# board.net
KiCad netlist of a schematic drawn in EAGLE
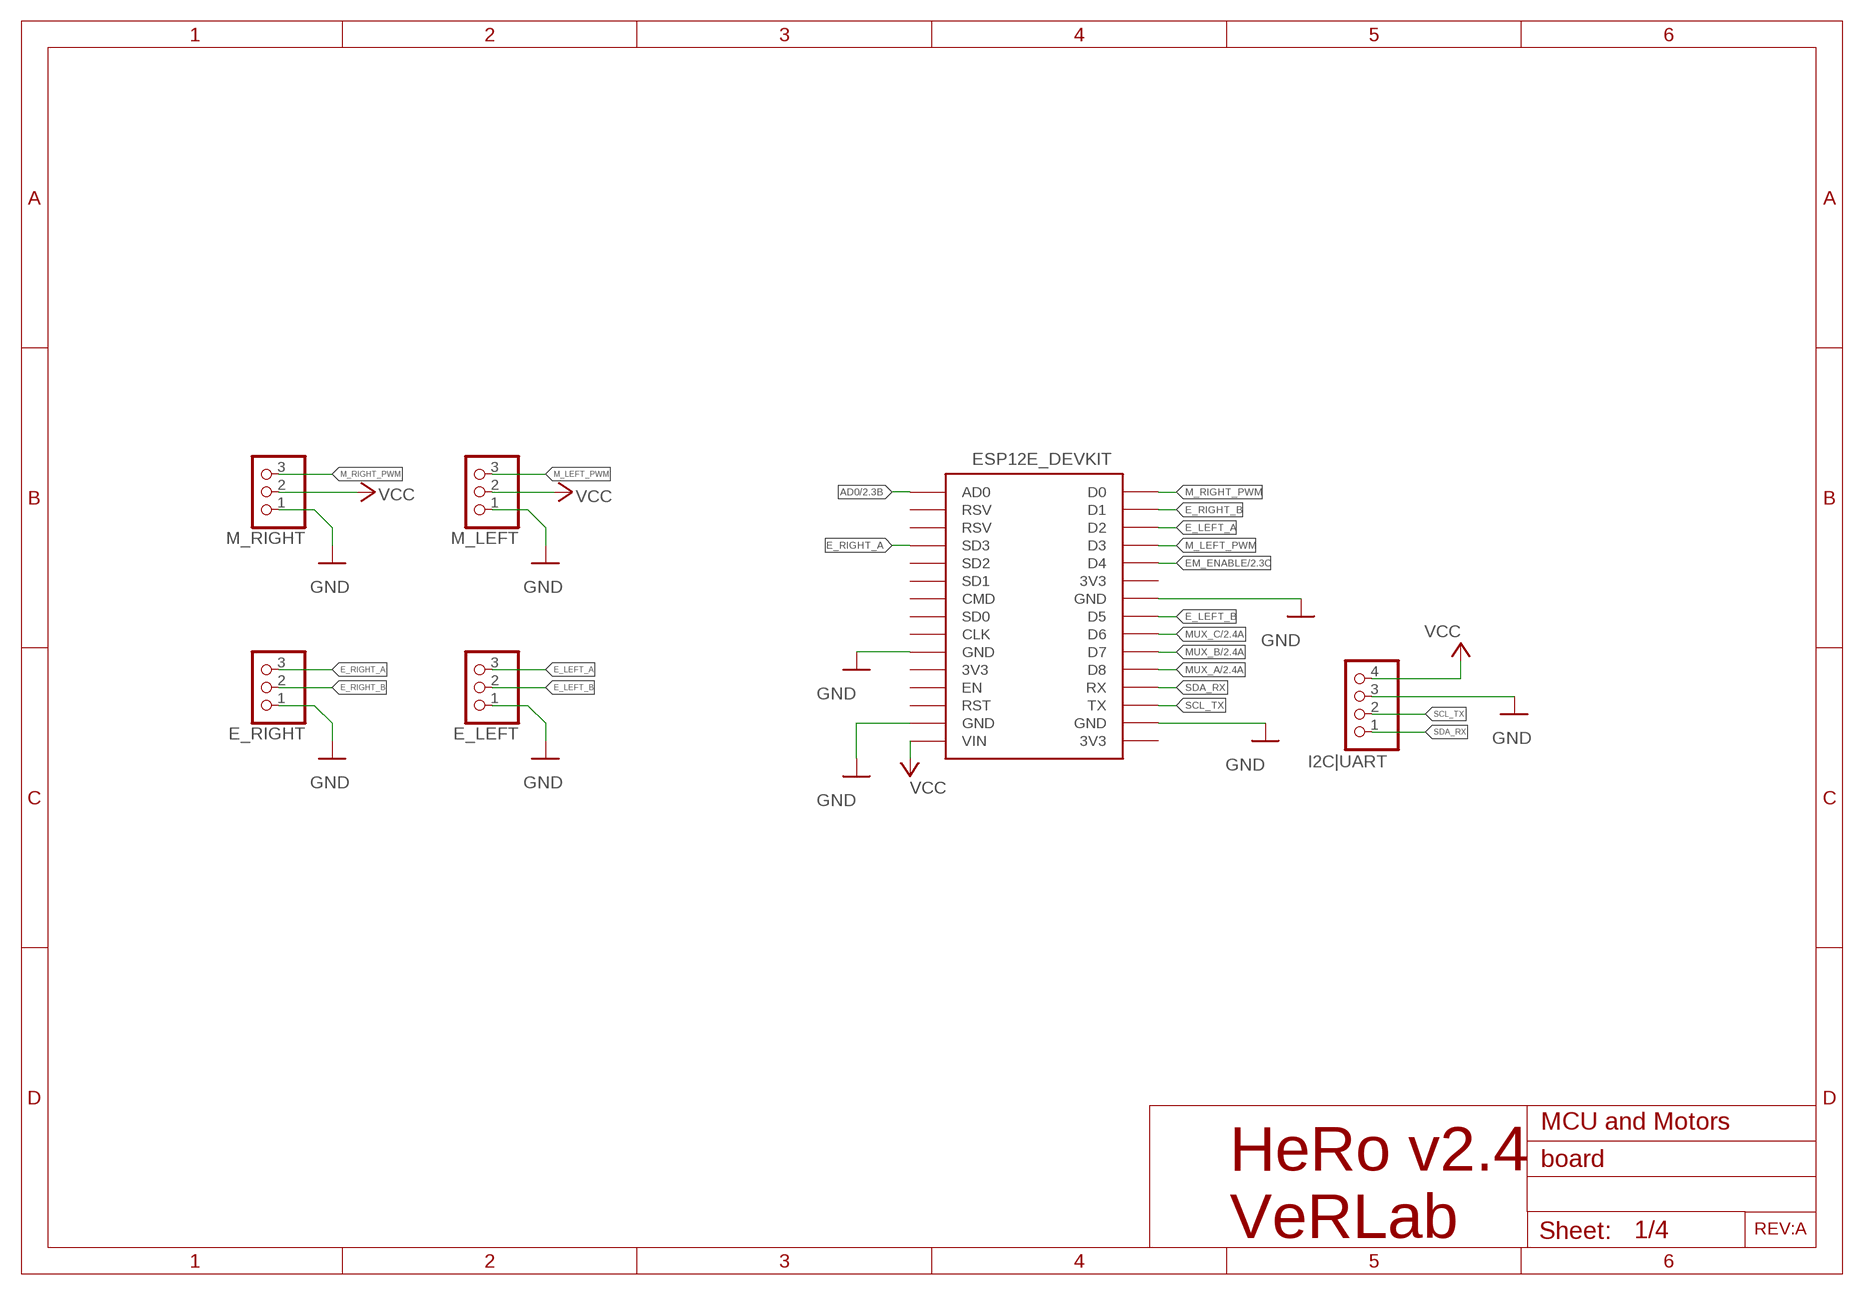
[diagram p0: schematic, sheet 1]
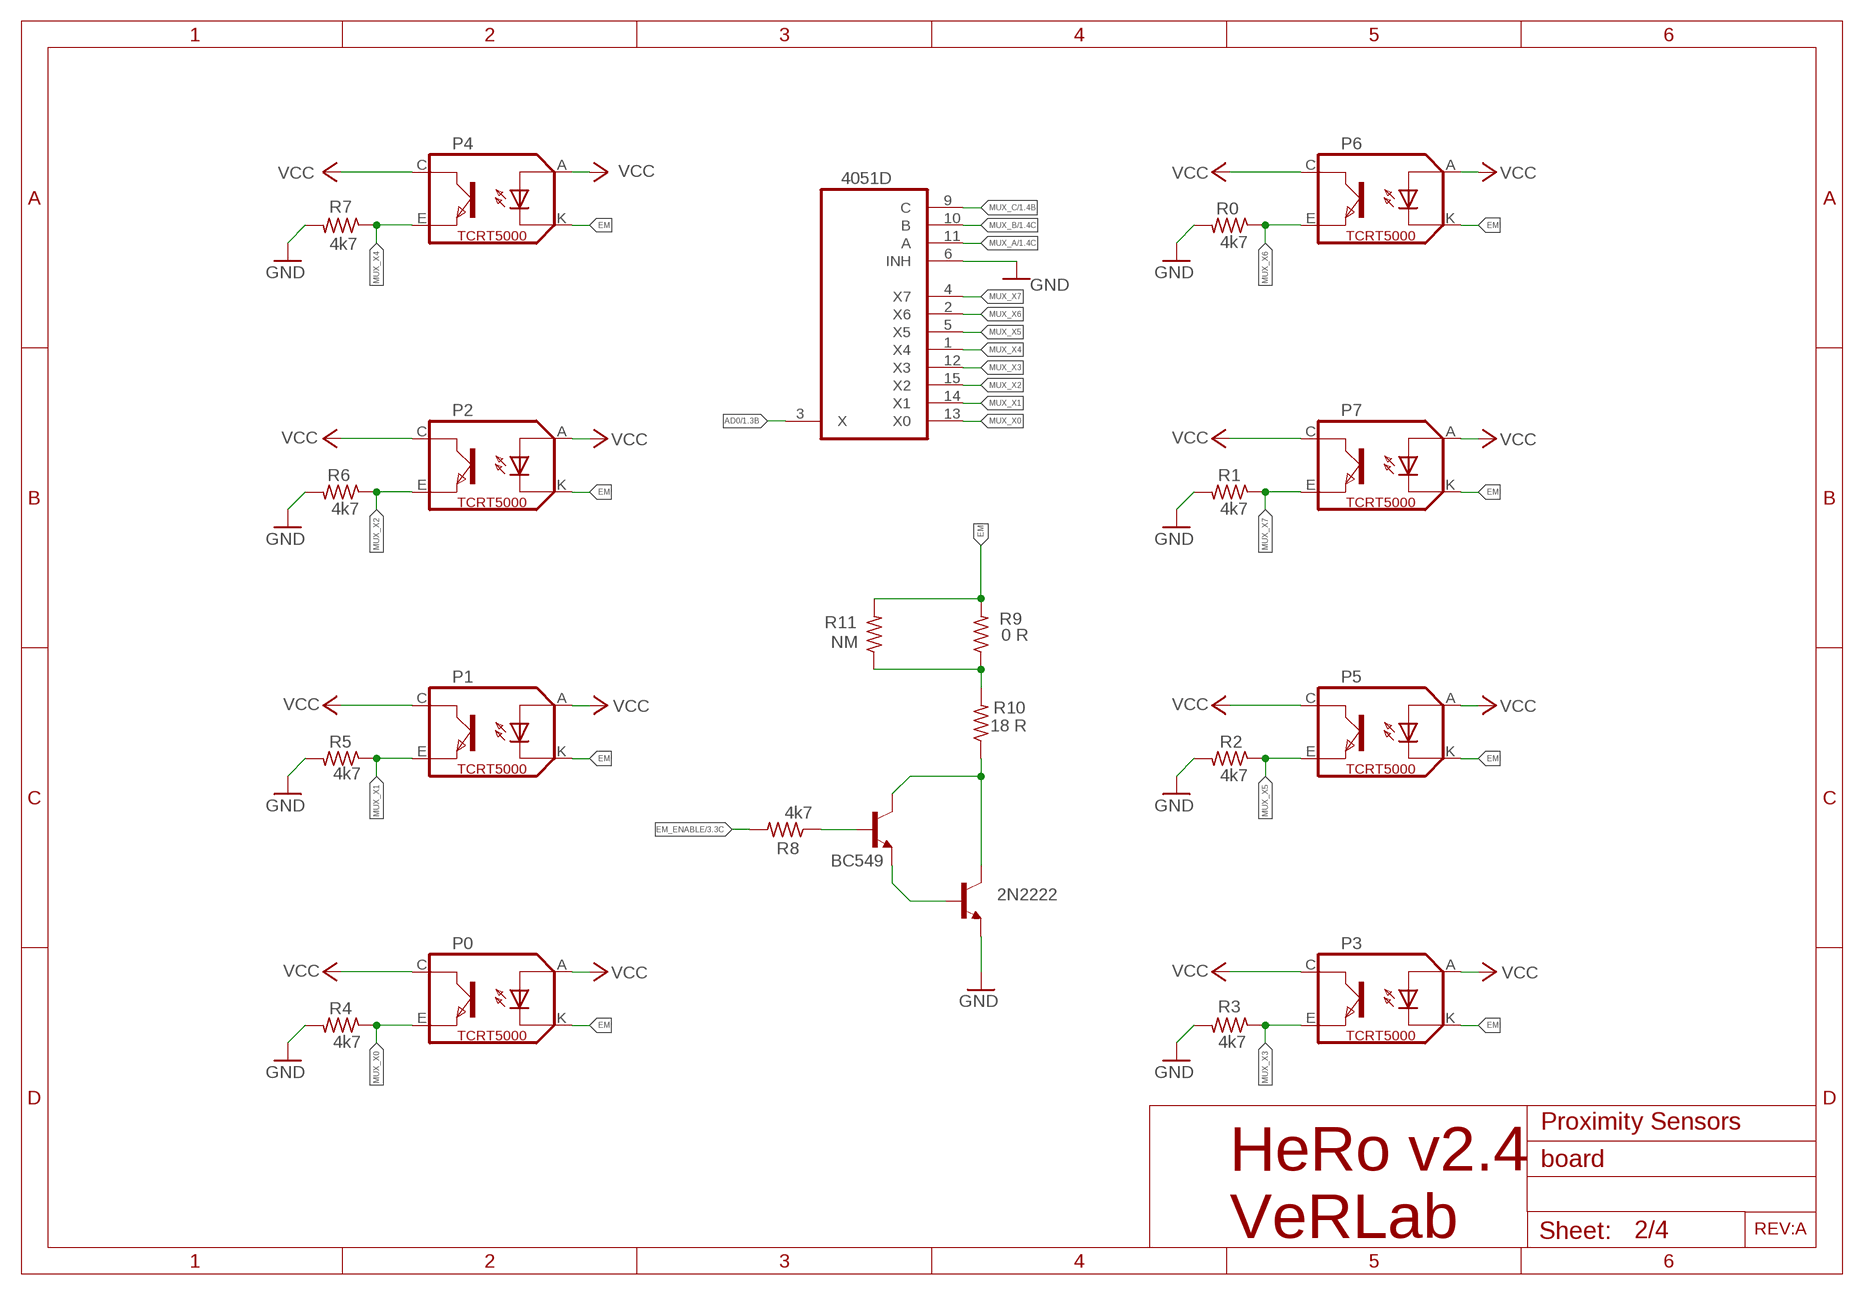
[diagram p1: schematic, sheet 2]
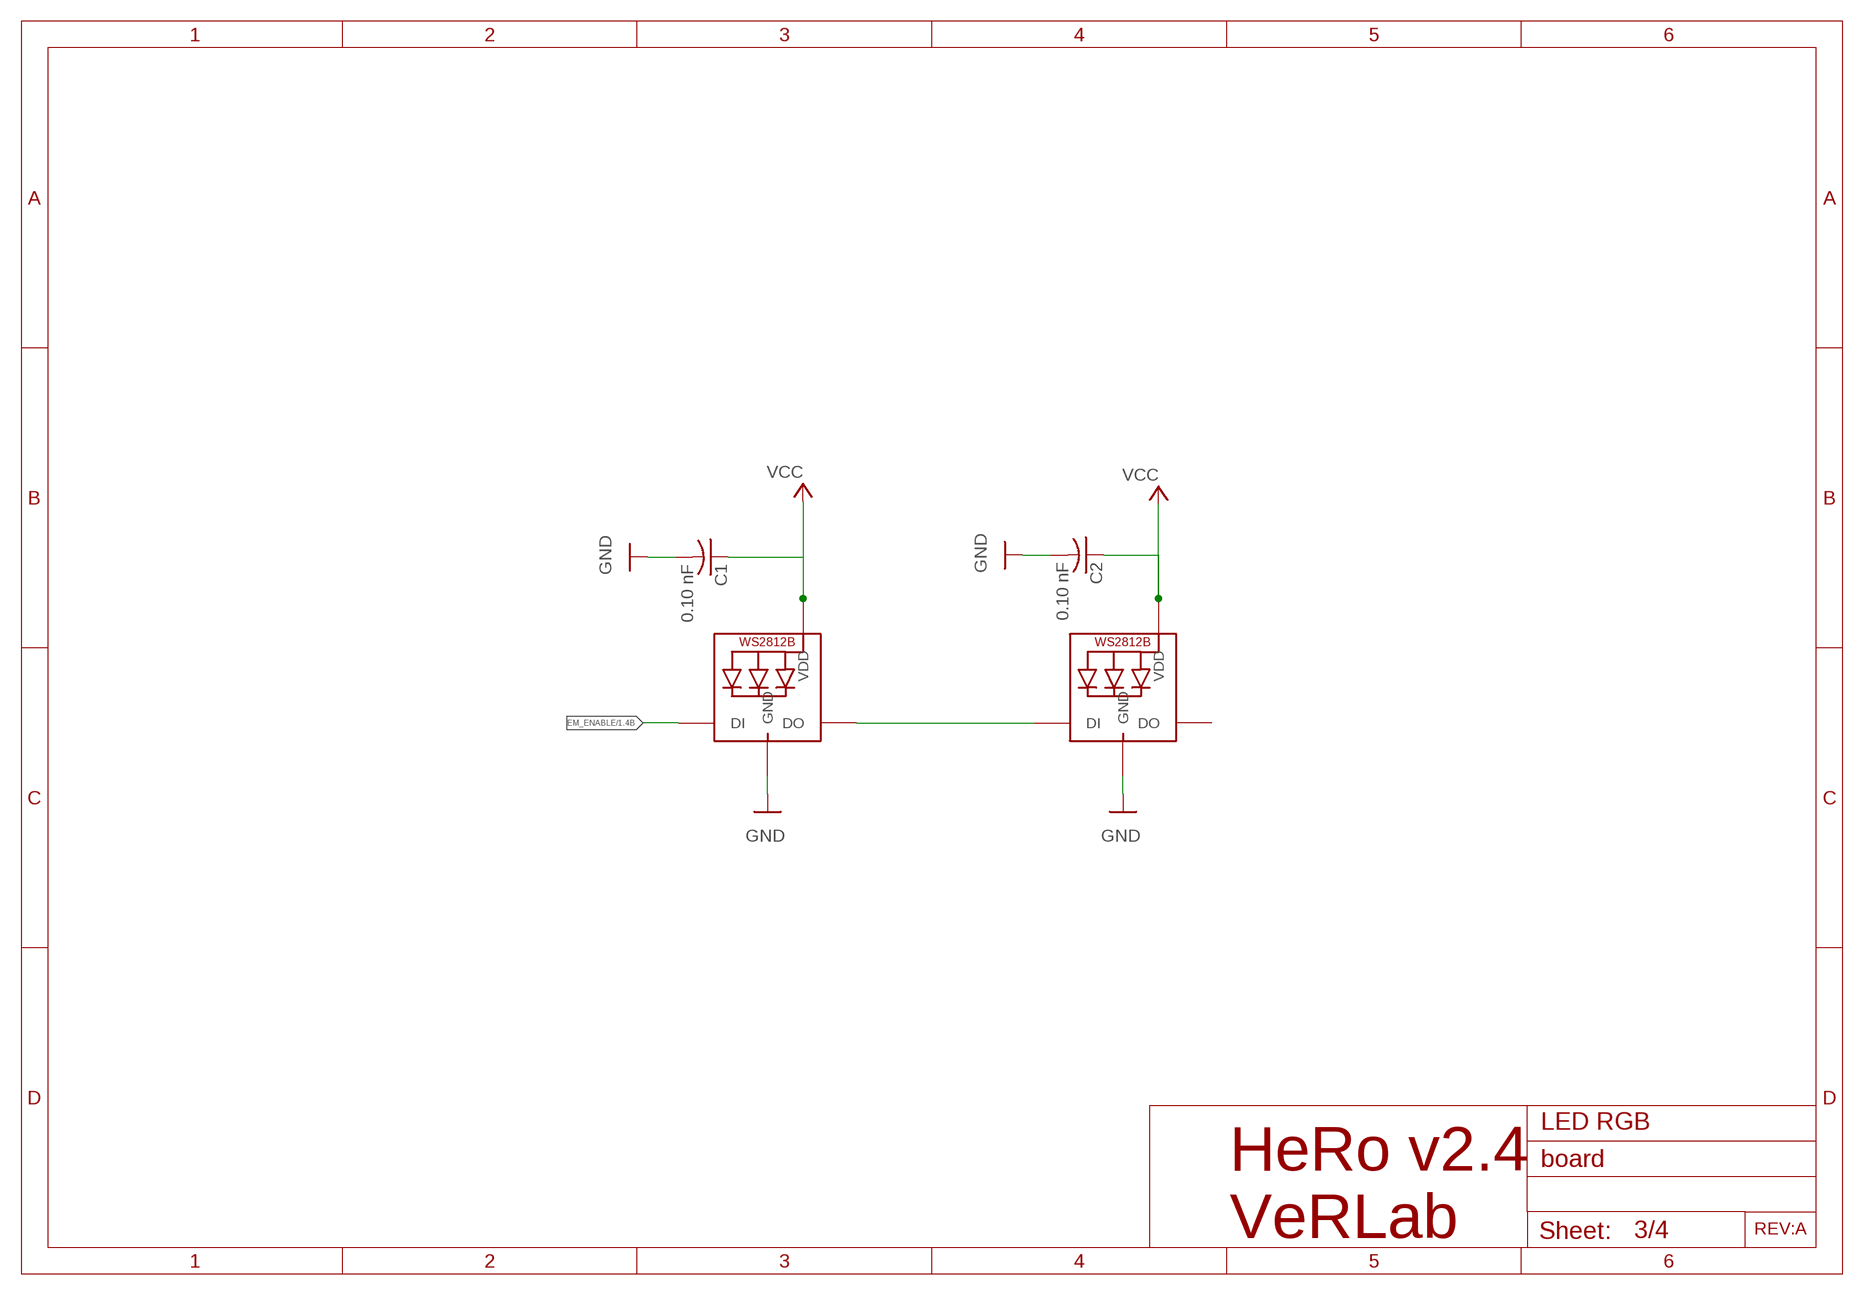
[diagram p2: schematic, sheet 3]
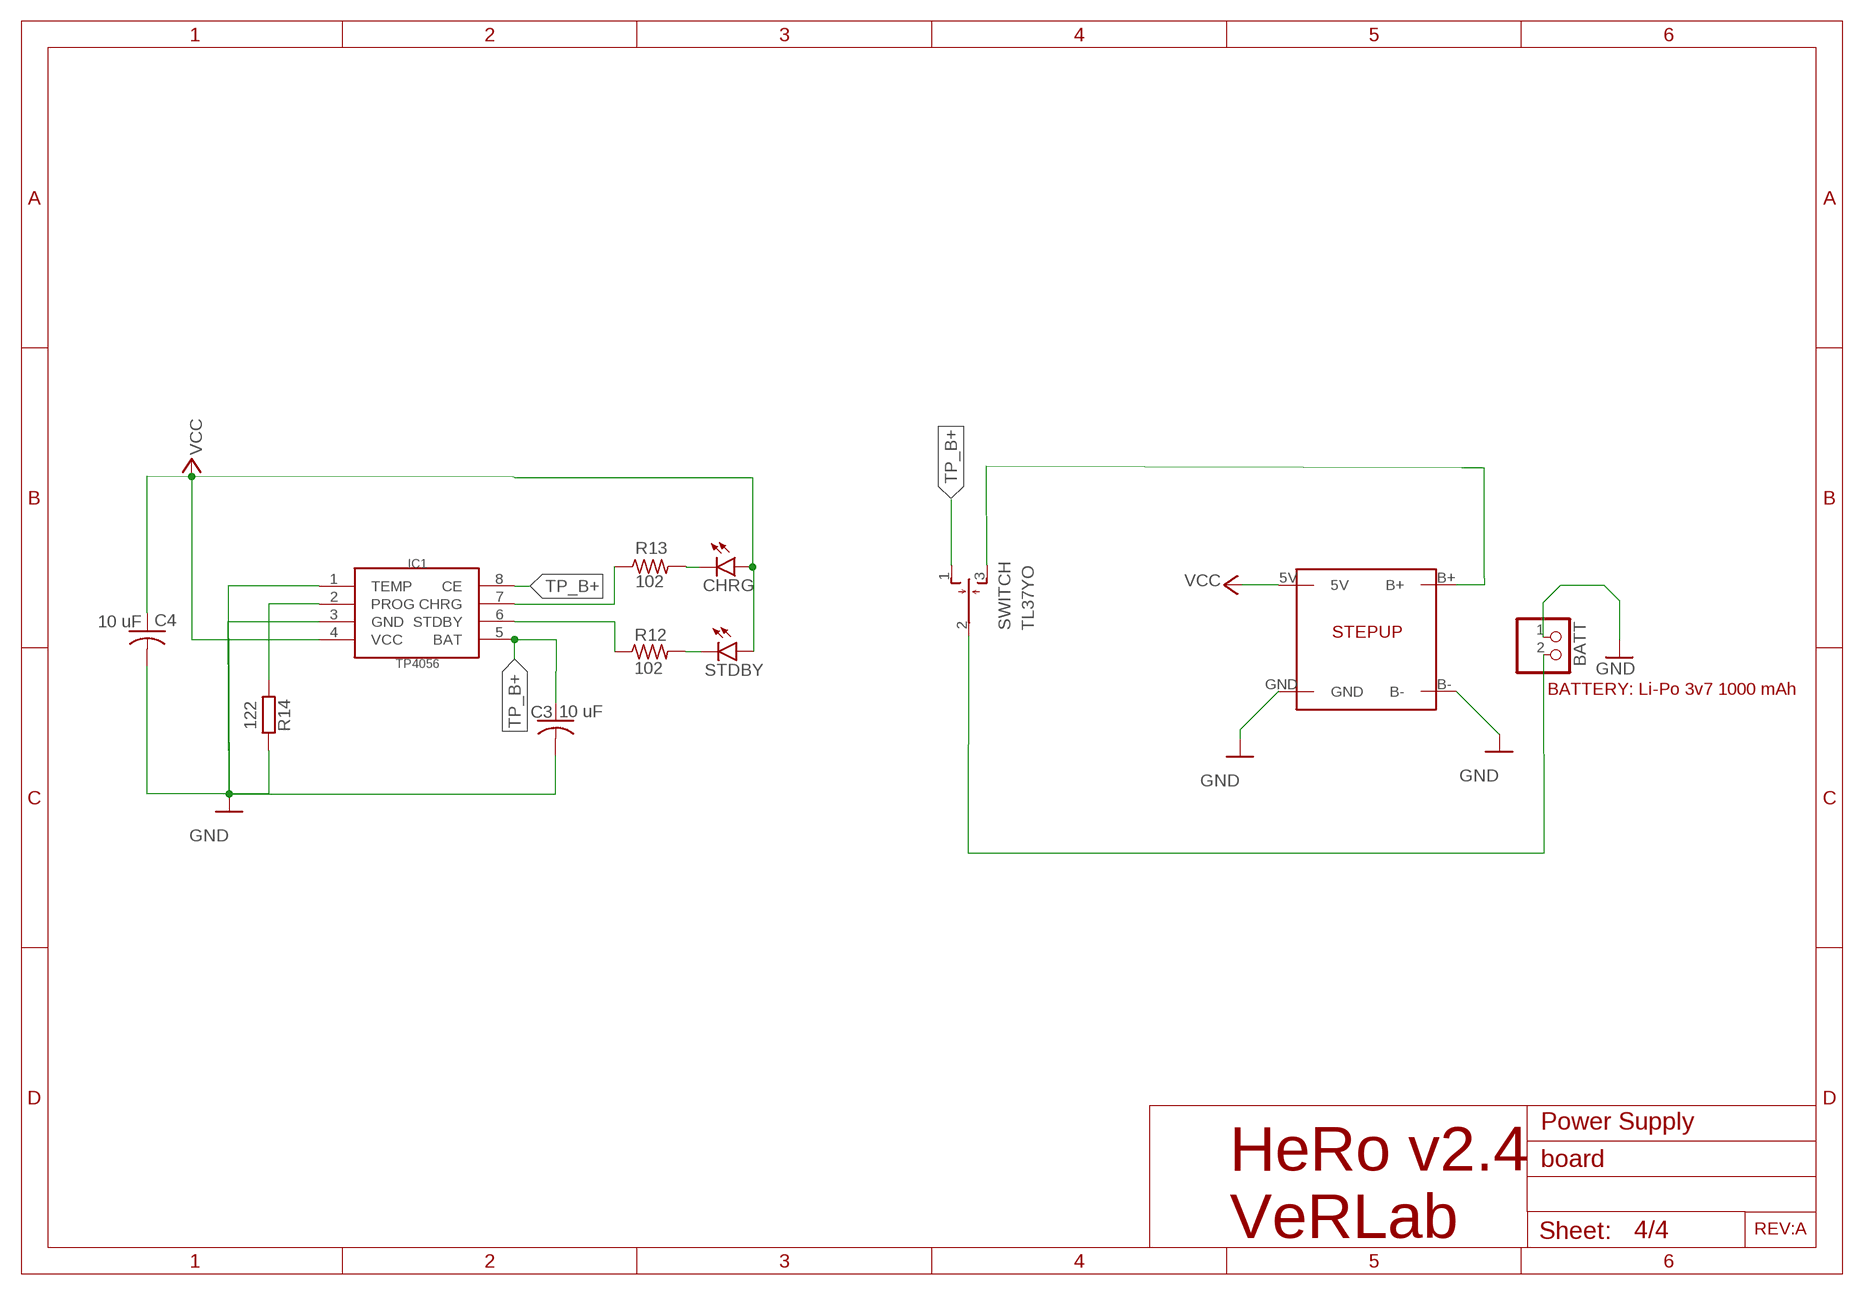
[diagram p3: schematic, sheet 4]

(export (version "E")
  (design (tool "Eeschema 10.0.6"))
  (components
    (comp (ref "C1")
      (value "0.10 nF")
      (footprint "eagle-import:C0603")
      (libsource (lib "eagle-import") (part "C-USC0603"))
    )
    (comp (ref "C2")
      (value "0.10 nF")
      (footprint "eagle-import:C0603")
      (libsource (lib "eagle-import") (part "C-USC0603"))
    )
    (comp (ref "LED0")
      (value "WS2812B5050")
      (footprint "eagle-import:WS2812B")
      (libsource (lib "eagle-import") (part "WS2812B5050"))
    )
    (comp (ref "LED1")
      (value "WS2812B5050")
      (footprint "eagle-import:WS2812B")
      (libsource (lib "eagle-import") (part "WS2812B5050"))
    )
    (comp (ref "BATT")
      (value "PINHD-1X2")
      (footprint "eagle-import:1X02")
      (libsource (lib "eagle-import") (part "PINHD-1X2"))
    )
    (comp (ref "C3")
      (value "10 uF")
      (footprint "eagle-import:C0603")
      (libsource (lib "eagle-import") (part "resistor_348_C-USC0603"))
    )
    (comp (ref "C4")
      (value "10 uF")
      (footprint "eagle-import:C0603")
      (libsource (lib "eagle-import") (part "resistor_348_C-USC0603"))
    )
    (comp (ref "CHRG")
      (value "LEDCHIP-LED0603")
      (footprint "eagle-import:CHIP-LED0603")
      (libsource (lib "eagle-import") (part "LEDCHIP-LED0603"))
    )
    (comp (ref "IC1")
      (value "TP4056")
      (footprint "eagle-import:SOP-8")
      (libsource (lib "eagle-import") (part "TP4056"))
    )
    (comp (ref "OS1")
      (value "STEPUP")
      (footprint "eagle-import:STEPUP")
      (libsource (lib "eagle-import") (part "STEPUP"))
    )
    (comp (ref "R12")
      (value "102")
      (footprint "eagle-import:R0603")
      (libsource (lib "eagle-import") (part "resistor_348_R-US_R0603"))
    )
    (comp (ref "R13")
      (value "102")
      (footprint "eagle-import:R0603")
      (libsource (lib "eagle-import") (part "resistor_348_R-US_R0603"))
    )
    (comp (ref "R14")
      (value "122")
      (footprint "eagle-import:R0603")
      (libsource (lib "eagle-import") (part "R-EU_R0603"))
    )
    (comp (ref "STDBY")
      (value "LEDCHIP-LED0603")
      (footprint "eagle-import:CHIP-LED0603")
      (libsource (lib "eagle-import") (part "LEDCHIP-LED0603"))
    )
    (comp (ref "SWITCH")
      (value "TL37YO")
      (footprint "eagle-import:TL3XYO")
      (libsource (lib "eagle-import") (part "TL37YO"))
    )
    (comp (ref "E_LEFT")
      (value "PINHD-1X3")
      (footprint "eagle-import:1X03")
      (libsource (lib "eagle-import") (part "PINHD-1X3"))
    )
    (comp (ref "E_RIGHT")
      (value "PINHD-1X3")
      (footprint "eagle-import:1X03")
      (libsource (lib "eagle-import") (part "PINHD-1X3"))
    )
    (comp (ref "I2C|UART")
      (value "PINHD-1X4")
      (footprint "eagle-import:1X04")
      (libsource (lib "eagle-import") (part "PINHD-1X4"))
    )
    (comp (ref "M_LEFT")
      (value "PINHD-1X3")
      (footprint "eagle-import:1X03")
      (libsource (lib "eagle-import") (part "PINHD-1X3"))
    )
    (comp (ref "M_RIGHT")
      (value "PINHD-1X3")
      (footprint "eagle-import:1X03")
      (libsource (lib "eagle-import") (part "PINHD-1X3"))
    )
    (comp (ref "U$1")
      (value "ESP12E_DEVKIT")
      (footprint "eagle-import:ESP12E_DEVKIT")
      (libsource (lib "eagle-import") (part "ESP12E_DEVKIT"))
    )
    (comp (ref "BC549")
      (value "BC549-NPN-TO92-CBE")
      (footprint "eagle-import:TO92-CBE")
      (fields (field (name "SPICEPREFIX") "J"))
      (libsource (lib "eagle-import") (part "-NPN-TO92-CBEBC549"))
    )
    (comp (ref "IC2")
      (value "4051D")
      (footprint "eagle-import:SO16")
      (libsource (lib "eagle-import") (part "4051D"))
    )
    (comp (ref "P0")
      (value "TCRT5000")
      (footprint "eagle-import:TCRT5000")
      (libsource (lib "eagle-import") (part "TCRT5000"))
    )
    (comp (ref "P1")
      (value "TCRT5000")
      (footprint "eagle-import:TCRT5000")
      (libsource (lib "eagle-import") (part "TCRT5000"))
    )
    (comp (ref "P2")
      (value "TCRT5000")
      (footprint "eagle-import:TCRT5000")
      (libsource (lib "eagle-import") (part "TCRT5000"))
    )
    (comp (ref "P3")
      (value "TCRT5000")
      (footprint "eagle-import:TCRT5000")
      (libsource (lib "eagle-import") (part "TCRT5000"))
    )
    (comp (ref "P4")
      (value "TCRT5000")
      (footprint "eagle-import:TCRT5000")
      (libsource (lib "eagle-import") (part "TCRT5000"))
    )
    (comp (ref "P5")
      (value "TCRT5000")
      (footprint "eagle-import:TCRT5000")
      (libsource (lib "eagle-import") (part "TCRT5000"))
    )
    (comp (ref "P6")
      (value "TCRT5000")
      (footprint "eagle-import:TCRT5000")
      (libsource (lib "eagle-import") (part "TCRT5000"))
    )
    (comp (ref "P7")
      (value "TCRT5000")
      (footprint "eagle-import:TCRT5000")
      (libsource (lib "eagle-import") (part "TCRT5000"))
    )
    (comp (ref "R0")
      (value "4k7")
      (footprint "eagle-import:M0805")
      (libsource (lib "eagle-import") (part "R-US_M0805"))
    )
    (comp (ref "R1")
      (value "4k7")
      (footprint "eagle-import:M0805")
      (libsource (lib "eagle-import") (part "R-US_M0805"))
    )
    (comp (ref "R2")
      (value "4k7")
      (footprint "eagle-import:M0805")
      (libsource (lib "eagle-import") (part "R-US_M0805"))
    )
    (comp (ref "R3")
      (value "4k7")
      (footprint "eagle-import:M0805")
      (libsource (lib "eagle-import") (part "R-US_M0805"))
    )
    (comp (ref "R4")
      (value "4k7")
      (footprint "eagle-import:M0805")
      (libsource (lib "eagle-import") (part "R-US_M0805"))
    )
    (comp (ref "R5")
      (value "4k7")
      (footprint "eagle-import:M0805")
      (libsource (lib "eagle-import") (part "R-US_M0805"))
    )
    (comp (ref "R6")
      (value "4k7")
      (footprint "eagle-import:M0805")
      (libsource (lib "eagle-import") (part "R-US_M0805"))
    )
    (comp (ref "R7")
      (value "4k7")
      (footprint "eagle-import:M0805")
      (libsource (lib "eagle-import") (part "R-US_M0805"))
    )
    (comp (ref "R8")
      (value "4k7")
      (footprint "eagle-import:R0805")
      (fields (field (name "SPICEPREFIX") "R"))
      (libsource (lib "eagle-import") (part "resistor_348_R-US_R0805"))
    )
    (comp (ref "R9")
      (value "0 R")
      (footprint "eagle-import:R0805")
      (fields (field (name "SPICEPREFIX") "R"))
      (libsource (lib "eagle-import") (part "resistor_348_R-US_R0805"))
    )
    (comp (ref "R10")
      (value "18 R")
      (footprint "eagle-import:R0805")
      (fields (field (name "SPICEPREFIX") "R"))
      (libsource (lib "eagle-import") (part "resistor_348_R-US_R0805"))
    )
    (comp (ref "R11")
      (value "NM")
      (footprint "eagle-import:R0805")
      (fields (field (name "SPICEPREFIX") "R"))
      (libsource (lib "eagle-import") (part "resistor_348_R-US_R0805"))
    )
    (comp (ref "T5")
      (value "2N2222")
      (footprint "eagle-import:TO92-EBC-OVAL")
      (fields (field (name "SPICEPREFIX") "J"))
      (libsource (lib "eagle-import") (part "2N2222"))
    )
  )
  (nets
    (net (code "1") (name "AD0") (class "Default")
      (node (ref "IC2") (pin "3") (pinfunction "X_3") (pintype "bidirectional"))
      (node (ref "U$1") (pin "AD0") (pinfunction "AD0_AD0") (pintype "bidirectional"))
    )
    (net (code "2") (name "EM") (class "Default")
      (node (ref "P0") (pin "K") (pinfunction "CATHODE_K") (pintype "passive"))
      (node (ref "P1") (pin "K") (pinfunction "CATHODE_K") (pintype "passive"))
      (node (ref "P2") (pin "K") (pinfunction "CATHODE_K") (pintype "passive"))
      (node (ref "P3") (pin "K") (pinfunction "CATHODE_K") (pintype "passive"))
      (node (ref "P4") (pin "K") (pinfunction "CATHODE_K") (pintype "passive"))
      (node (ref "P5") (pin "K") (pinfunction "CATHODE_K") (pintype "passive"))
      (node (ref "P6") (pin "K") (pinfunction "CATHODE_K") (pintype "passive"))
      (node (ref "P7") (pin "K") (pinfunction "CATHODE_K") (pintype "passive"))
      (node (ref "R11") (pin "2") (pinfunction "2_2") (pintype "passive"))
      (node (ref "R9") (pin "2") (pinfunction "2_2") (pintype "passive"))
    )
    (net (code "3") (name "EM_ENABLE") (class "Default")
      (node (ref "LED0") (pin "4-DIN") (pinfunction "DI_4-DIN") (pintype "input"))
      (node (ref "R8") (pin "2") (pinfunction "2_2") (pintype "passive"))
      (node (ref "U$1") (pin "D4") (pinfunction "D4_D4") (pintype "bidirectional"))
    )
    (net (code "4") (name "E_LEFT_A") (class "Default")
      (node (ref "E_LEFT") (pin "3") (pinfunction "3_3") (pintype "passive"))
      (node (ref "U$1") (pin "D2") (pinfunction "D2_D2") (pintype "bidirectional"))
    )
    (net (code "5") (name "E_LEFT_B") (class "Default")
      (node (ref "E_LEFT") (pin "2") (pinfunction "2_2") (pintype "passive"))
      (node (ref "U$1") (pin "D5") (pinfunction "D5_D5") (pintype "bidirectional"))
    )
    (net (code "6") (name "E_RIGHT_A") (class "Default")
      (node (ref "E_RIGHT") (pin "3") (pinfunction "3_3") (pintype "passive"))
      (node (ref "U$1") (pin "SD3") (pinfunction "SD3_SD3") (pintype "bidirectional"))
    )
    (net (code "7") (name "E_RIGHT_B") (class "Default")
      (node (ref "E_RIGHT") (pin "2") (pinfunction "2_2") (pintype "passive"))
      (node (ref "U$1") (pin "D1") (pinfunction "D1_D1") (pintype "bidirectional"))
    )
    (net (code "8") (name "GND") (class "Default")
      (node (ref "BATT") (pin "1") (pinfunction "1_1") (pintype "passive"))
      (node (ref "C1") (pin "2") (pinfunction "2_2") (pintype "passive"))
      (node (ref "C2") (pin "2") (pinfunction "2_2") (pintype "passive"))
      (node (ref "C3") (pin "2") (pinfunction "2_2") (pintype "passive"))
      (node (ref "C4") (pin "2") (pinfunction "2_2") (pintype "passive"))
      (node (ref "E_LEFT") (pin "1") (pinfunction "1_1") (pintype "passive"))
      (node (ref "E_RIGHT") (pin "1") (pinfunction "1_1") (pintype "passive"))
      (node (ref "I2C|UART") (pin "3") (pinfunction "3_3") (pintype "passive"))
      (node (ref "IC1") (pin "1") (pinfunction "TEMP_1") (pintype "bidirectional"))
      (node (ref "IC1") (pin "3") (pinfunction "GND_3") (pintype "bidirectional"))
      (node (ref "IC2") (pin "6") (pinfunction "INH_6") (pintype "input"))
      (node (ref "LED0") (pin "3-GND") (pinfunction "GND_3-GND") (pintype "power_in"))
      (node (ref "LED1") (pin "3-GND") (pinfunction "GND_3-GND") (pintype "power_in"))
      (node (ref "M_LEFT") (pin "1") (pinfunction "1_1") (pintype "passive"))
      (node (ref "M_RIGHT") (pin "1") (pinfunction "1_1") (pintype "passive"))
      (node (ref "OS1") (pin "B-") (pinfunction "B-_B-") (pintype "input"))
      (node (ref "OS1") (pin "GND") (pinfunction "GND_GND") (pintype "output"))
      (node (ref "R0") (pin "2") (pinfunction "2_2") (pintype "passive"))
      (node (ref "R1") (pin "2") (pinfunction "2_2") (pintype "passive"))
      (node (ref "R14") (pin "1") (pinfunction "1_1") (pintype "passive"))
      (node (ref "R2") (pin "2") (pinfunction "2_2") (pintype "passive"))
      (node (ref "R3") (pin "2") (pinfunction "2_2") (pintype "passive"))
      (node (ref "R4") (pin "2") (pinfunction "2_2") (pintype "passive"))
      (node (ref "R5") (pin "2") (pinfunction "2_2") (pintype "passive"))
      (node (ref "R6") (pin "2") (pinfunction "2_2") (pintype "passive"))
      (node (ref "R7") (pin "2") (pinfunction "2_2") (pintype "passive"))
      (node (ref "T5") (pin "E") (pinfunction "E_E") (pintype "passive"))
      (node (ref "U$1") (pin "GND@0") (pinfunction "GND_GND@0") (pintype "bidirectional"))
      (node (ref "U$1") (pin "GND@1") (pinfunction "GND_GND@1") (pintype "bidirectional"))
      (node (ref "U$1") (pin "GND@2") (pinfunction "GND_GND@2") (pintype "bidirectional"))
      (node (ref "U$1") (pin "GND@3") (pinfunction "GND_GND@3") (pintype "bidirectional"))
    )
    (net (code "9") (name "MUX_A") (class "Default")
      (node (ref "IC2") (pin "11") (pinfunction "A_11") (pintype "input"))
      (node (ref "U$1") (pin "D8") (pinfunction "D8_D8") (pintype "bidirectional"))
    )
    (net (code "10") (name "MUX_B") (class "Default")
      (node (ref "IC2") (pin "10") (pinfunction "B_10") (pintype "input"))
      (node (ref "U$1") (pin "D7") (pinfunction "D7_D7") (pintype "bidirectional"))
    )
    (net (code "11") (name "MUX_C") (class "Default")
      (node (ref "IC2") (pin "9") (pinfunction "C_9") (pintype "input"))
      (node (ref "U$1") (pin "D6") (pinfunction "D6_D6") (pintype "bidirectional"))
    )
    (net (code "12") (name "MUX_X0") (class "Default")
      (node (ref "IC2") (pin "13") (pinfunction "X0_13") (pintype "bidirectional"))
      (node (ref "P0") (pin "E") (pinfunction "EMITTER_E") (pintype "passive"))
      (node (ref "R4") (pin "1") (pinfunction "1_1") (pintype "passive"))
    )
    (net (code "13") (name "MUX_X1") (class "Default")
      (node (ref "IC2") (pin "14") (pinfunction "X1_14") (pintype "bidirectional"))
      (node (ref "P1") (pin "E") (pinfunction "EMITTER_E") (pintype "passive"))
      (node (ref "R5") (pin "1") (pinfunction "1_1") (pintype "passive"))
    )
    (net (code "14") (name "MUX_X2") (class "Default")
      (node (ref "IC2") (pin "15") (pinfunction "X2_15") (pintype "bidirectional"))
      (node (ref "P2") (pin "E") (pinfunction "EMITTER_E") (pintype "passive"))
      (node (ref "R6") (pin "1") (pinfunction "1_1") (pintype "passive"))
    )
    (net (code "15") (name "MUX_X3") (class "Default")
      (node (ref "IC2") (pin "12") (pinfunction "X3_12") (pintype "bidirectional"))
      (node (ref "P3") (pin "E") (pinfunction "EMITTER_E") (pintype "passive"))
      (node (ref "R3") (pin "1") (pinfunction "1_1") (pintype "passive"))
    )
    (net (code "16") (name "MUX_X4") (class "Default")
      (node (ref "IC2") (pin "1") (pinfunction "X4_1") (pintype "bidirectional"))
      (node (ref "P4") (pin "E") (pinfunction "EMITTER_E") (pintype "passive"))
      (node (ref "R7") (pin "1") (pinfunction "1_1") (pintype "passive"))
    )
    (net (code "17") (name "MUX_X5") (class "Default")
      (node (ref "IC2") (pin "5") (pinfunction "X5_5") (pintype "bidirectional"))
      (node (ref "P5") (pin "E") (pinfunction "EMITTER_E") (pintype "passive"))
      (node (ref "R2") (pin "1") (pinfunction "1_1") (pintype "passive"))
    )
    (net (code "18") (name "MUX_X6") (class "Default")
      (node (ref "IC2") (pin "2") (pinfunction "X6_2") (pintype "bidirectional"))
      (node (ref "P6") (pin "E") (pinfunction "EMITTER_E") (pintype "passive"))
      (node (ref "R0") (pin "1") (pinfunction "1_1") (pintype "passive"))
    )
    (net (code "19") (name "MUX_X7") (class "Default")
      (node (ref "IC2") (pin "4") (pinfunction "X7_4") (pintype "bidirectional"))
      (node (ref "P7") (pin "E") (pinfunction "EMITTER_E") (pintype "passive"))
      (node (ref "R1") (pin "1") (pinfunction "1_1") (pintype "passive"))
    )
    (net (code "20") (name "M_LEFT_PWM") (class "Default")
      (node (ref "M_LEFT") (pin "3") (pinfunction "3_3") (pintype "passive"))
      (node (ref "U$1") (pin "D3") (pinfunction "D3_D3") (pintype "bidirectional"))
    )
    (net (code "21") (name "M_RIGHT_PWM") (class "Default")
      (node (ref "M_RIGHT") (pin "3") (pinfunction "3_3") (pintype "passive"))
      (node (ref "U$1") (pin "D0") (pinfunction "D0_D0") (pintype "bidirectional"))
    )
    (net (code "22") (name "Net-(BC549-PadB)") (class "Default")
      (node (ref "BC549") (pin "B") (pinfunction "B_B") (pintype "passive"))
      (node (ref "R8") (pin "1") (pinfunction "1_1") (pintype "passive"))
    )
    (net (code "23") (name "Net-(BC549-PadC)") (class "Default")
      (node (ref "BC549") (pin "C") (pinfunction "C_C") (pintype "passive"))
      (node (ref "R10") (pin "1") (pinfunction "1_1") (pintype "passive"))
      (node (ref "T5") (pin "C") (pinfunction "C_C") (pintype "passive"))
    )
    (net (code "24") (name "Net-(BC549-PadE)") (class "Default")
      (node (ref "BC549") (pin "E") (pinfunction "E_E") (pintype "passive"))
      (node (ref "T5") (pin "B") (pinfunction "B_B") (pintype "passive"))
    )
    (net (code "25") (name "Net-(CHRG-PadA)") (class "Default")
      (node (ref "CHRG") (pin "A") (pinfunction "A_A") (pintype "passive"))
      (node (ref "STDBY") (pin "A") (pinfunction "A_A") (pintype "passive"))
    )
    (net (code "26") (name "Net-(CHRG-PadC)") (class "Default")
      (node (ref "CHRG") (pin "C") (pinfunction "C_C") (pintype "passive"))
      (node (ref "R13") (pin "2") (pinfunction "2_2") (pintype "passive"))
    )
    (net (code "27") (name "Net-(IC1-CHRG)") (class "Default")
      (node (ref "IC1") (pin "7") (pinfunction "CHRG_7") (pintype "bidirectional"))
      (node (ref "R13") (pin "1") (pinfunction "1_1") (pintype "passive"))
    )
    (net (code "28") (name "Net-(IC1-PROG)") (class "Default")
      (node (ref "IC1") (pin "2") (pinfunction "PROG_2") (pintype "bidirectional"))
      (node (ref "R14") (pin "2") (pinfunction "2_2") (pintype "passive"))
    )
    (net (code "29") (name "Net-(IC1-STDBY)") (class "Default")
      (node (ref "IC1") (pin "6") (pinfunction "STDBY_6") (pintype "bidirectional"))
      (node (ref "R12") (pin "1") (pinfunction "1_1") (pintype "passive"))
    )
    (net (code "30") (name "Net-(LED0-DO)") (class "Default")
      (node (ref "LED0") (pin "2-DOUT") (pinfunction "DO_2-DOUT") (pintype "output"))
      (node (ref "LED1") (pin "4-DIN") (pinfunction "DI_4-DIN") (pintype "input"))
    )
    (net (code "31") (name "Net-(R10-Pad2)") (class "Default")
      (node (ref "R10") (pin "2") (pinfunction "2_2") (pintype "passive"))
      (node (ref "R11") (pin "1") (pinfunction "1_1") (pintype "passive"))
      (node (ref "R9") (pin "1") (pinfunction "1_1") (pintype "passive"))
    )
    (net (code "32") (name "Net-(R12-Pad2)") (class "Default")
      (node (ref "R12") (pin "2") (pinfunction "2_2") (pintype "passive"))
      (node (ref "STDBY") (pin "C") (pinfunction "C_C") (pintype "passive"))
    )
    (net (code "33") (name "Net-(SWITCH-P)") (class "Default")
      (node (ref "BATT") (pin "2") (pinfunction "2_2") (pintype "passive"))
      (node (ref "SWITCH") (pin "2") (pinfunction "P_2") (pintype "passive"))
    )
    (net (code "34") (name "Net-(SWITCH-S)") (class "Default")
      (node (ref "OS1") (pin "B+") (pinfunction "B+_B+") (pintype "input"))
      (node (ref "SWITCH") (pin "3") (pinfunction "S_3") (pintype "passive"))
    )
    (net (code "35") (name "SCL_TX") (class "Default")
      (node (ref "I2C|UART") (pin "2") (pinfunction "2_2") (pintype "passive"))
      (node (ref "U$1") (pin "TX") (pinfunction "TX_TX") (pintype "bidirectional"))
    )
    (net (code "36") (name "SDA_RX") (class "Default")
      (node (ref "I2C|UART") (pin "1") (pinfunction "1_1") (pintype "passive"))
      (node (ref "U$1") (pin "RX") (pinfunction "RX_RX") (pintype "bidirectional"))
    )
    (net (code "37") (name "TP_B+") (class "Default")
      (node (ref "C3") (pin "1") (pinfunction "1_1") (pintype "passive"))
      (node (ref "IC1") (pin "5") (pinfunction "BAT_5") (pintype "bidirectional"))
      (node (ref "IC1") (pin "8") (pinfunction "CE_8") (pintype "bidirectional"))
      (node (ref "SWITCH") (pin "1") (pinfunction "O_1") (pintype "passive"))
    )
    (net (code "38") (name "VCC") (class "Default")
      (node (ref "C1") (pin "1") (pinfunction "1_1") (pintype "passive"))
      (node (ref "C2") (pin "1") (pinfunction "1_1") (pintype "passive"))
      (node (ref "C4") (pin "1") (pinfunction "1_1") (pintype "passive"))
      (node (ref "I2C|UART") (pin "4") (pinfunction "4_4") (pintype "passive"))
      (node (ref "IC1") (pin "4") (pinfunction "VCC_4") (pintype "bidirectional"))
      (node (ref "LED0") (pin "1-VDD") (pinfunction "VDD_1-VDD") (pintype "power_in"))
      (node (ref "LED1") (pin "1-VDD") (pinfunction "VDD_1-VDD") (pintype "power_in"))
      (node (ref "M_LEFT") (pin "2") (pinfunction "2_2") (pintype "passive"))
      (node (ref "M_RIGHT") (pin "2") (pinfunction "2_2") (pintype "passive"))
      (node (ref "OS1") (pin "5V") (pinfunction "5V_5V") (pintype "output"))
      (node (ref "P0") (pin "A") (pinfunction "ANODE_A") (pintype "passive"))
      (node (ref "P0") (pin "C") (pinfunction "COLLECTOR_C") (pintype "passive"))
      (node (ref "P1") (pin "A") (pinfunction "ANODE_A") (pintype "passive"))
      (node (ref "P1") (pin "C") (pinfunction "COLLECTOR_C") (pintype "passive"))
      (node (ref "P2") (pin "A") (pinfunction "ANODE_A") (pintype "passive"))
      (node (ref "P2") (pin "C") (pinfunction "COLLECTOR_C") (pintype "passive"))
      (node (ref "P3") (pin "A") (pinfunction "ANODE_A") (pintype "passive"))
      (node (ref "P3") (pin "C") (pinfunction "COLLECTOR_C") (pintype "passive"))
      (node (ref "P4") (pin "A") (pinfunction "ANODE_A") (pintype "passive"))
      (node (ref "P4") (pin "C") (pinfunction "COLLECTOR_C") (pintype "passive"))
      (node (ref "P5") (pin "A") (pinfunction "ANODE_A") (pintype "passive"))
      (node (ref "P5") (pin "C") (pinfunction "COLLECTOR_C") (pintype "passive"))
      (node (ref "P6") (pin "A") (pinfunction "ANODE_A") (pintype "passive"))
      (node (ref "P6") (pin "C") (pinfunction "COLLECTOR_C") (pintype "passive"))
      (node (ref "P7") (pin "A") (pinfunction "ANODE_A") (pintype "passive"))
      (node (ref "P7") (pin "C") (pinfunction "COLLECTOR_C") (pintype "passive"))
      (node (ref "U$1") (pin "VIN") (pinfunction "VIN_VIN") (pintype "bidirectional"))
    )
    (net (code "39") (name "unconnected-(LED1-DO-Pad2-DOUT)") (class "Default")
      (node (ref "LED1") (pin "2-DOUT") (pinfunction "DO_2-DOUT") (pintype "output"))
    )
    (net (code "40") (name "unconnected-(U$1-3V3-Pad3V3@0)") (class "Default")
      (node (ref "U$1") (pin "3V3@0") (pinfunction "3V3_3V3@0") (pintype "bidirectional"))
    )
    (net (code "41") (name "unconnected-(U$1-3V3-Pad3V3@1)") (class "Default")
      (node (ref "U$1") (pin "3V3@1") (pinfunction "3V3_3V3@1") (pintype "bidirectional"))
    )
    (net (code "42") (name "unconnected-(U$1-3V3-Pad3V3@2)") (class "Default")
      (node (ref "U$1") (pin "3V3@2") (pinfunction "3V3_3V3@2") (pintype "bidirectional"))
    )
    (net (code "43") (name "unconnected-(U$1-PadCLK)") (class "Default")
      (node (ref "U$1") (pin "CLK") (pinfunction "CLK_CLK") (pintype "bidirectional"))
    )
    (net (code "44") (name "unconnected-(U$1-PadCMD)") (class "Default")
      (node (ref "U$1") (pin "CMD") (pinfunction "CMD_CMD") (pintype "bidirectional"))
    )
    (net (code "45") (name "unconnected-(U$1-PadEN)") (class "Default")
      (node (ref "U$1") (pin "EN") (pinfunction "EN_EN") (pintype "bidirectional"))
    )
    (net (code "46") (name "unconnected-(U$1-PadRST)") (class "Default")
      (node (ref "U$1") (pin "RST") (pinfunction "RST_RST") (pintype "bidirectional"))
    )
    (net (code "47") (name "unconnected-(U$1-PadSD0)") (class "Default")
      (node (ref "U$1") (pin "SD0") (pinfunction "SD0_SD0") (pintype "bidirectional"))
    )
    (net (code "48") (name "unconnected-(U$1-PadSD1)") (class "Default")
      (node (ref "U$1") (pin "SD1") (pinfunction "SD1_SD1") (pintype "bidirectional"))
    )
    (net (code "49") (name "unconnected-(U$1-PadSD2)") (class "Default")
      (node (ref "U$1") (pin "SD2") (pinfunction "SD2_SD2") (pintype "bidirectional"))
    )
    (net (code "50") (name "unconnected-(U$1-RSV-PadRSV@0)") (class "Default")
      (node (ref "U$1") (pin "RSV@0") (pinfunction "RSV_RSV@0") (pintype "bidirectional"))
    )
    (net (code "51") (name "unconnected-(U$1-RSV-PadRSV@1)") (class "Default")
      (node (ref "U$1") (pin "RSV@1") (pinfunction "RSV_RSV@1") (pintype "bidirectional"))
    )
  )
)
